# FPGA_Supply.net
KiCad netlist of a schematic drawn in Altium Designer
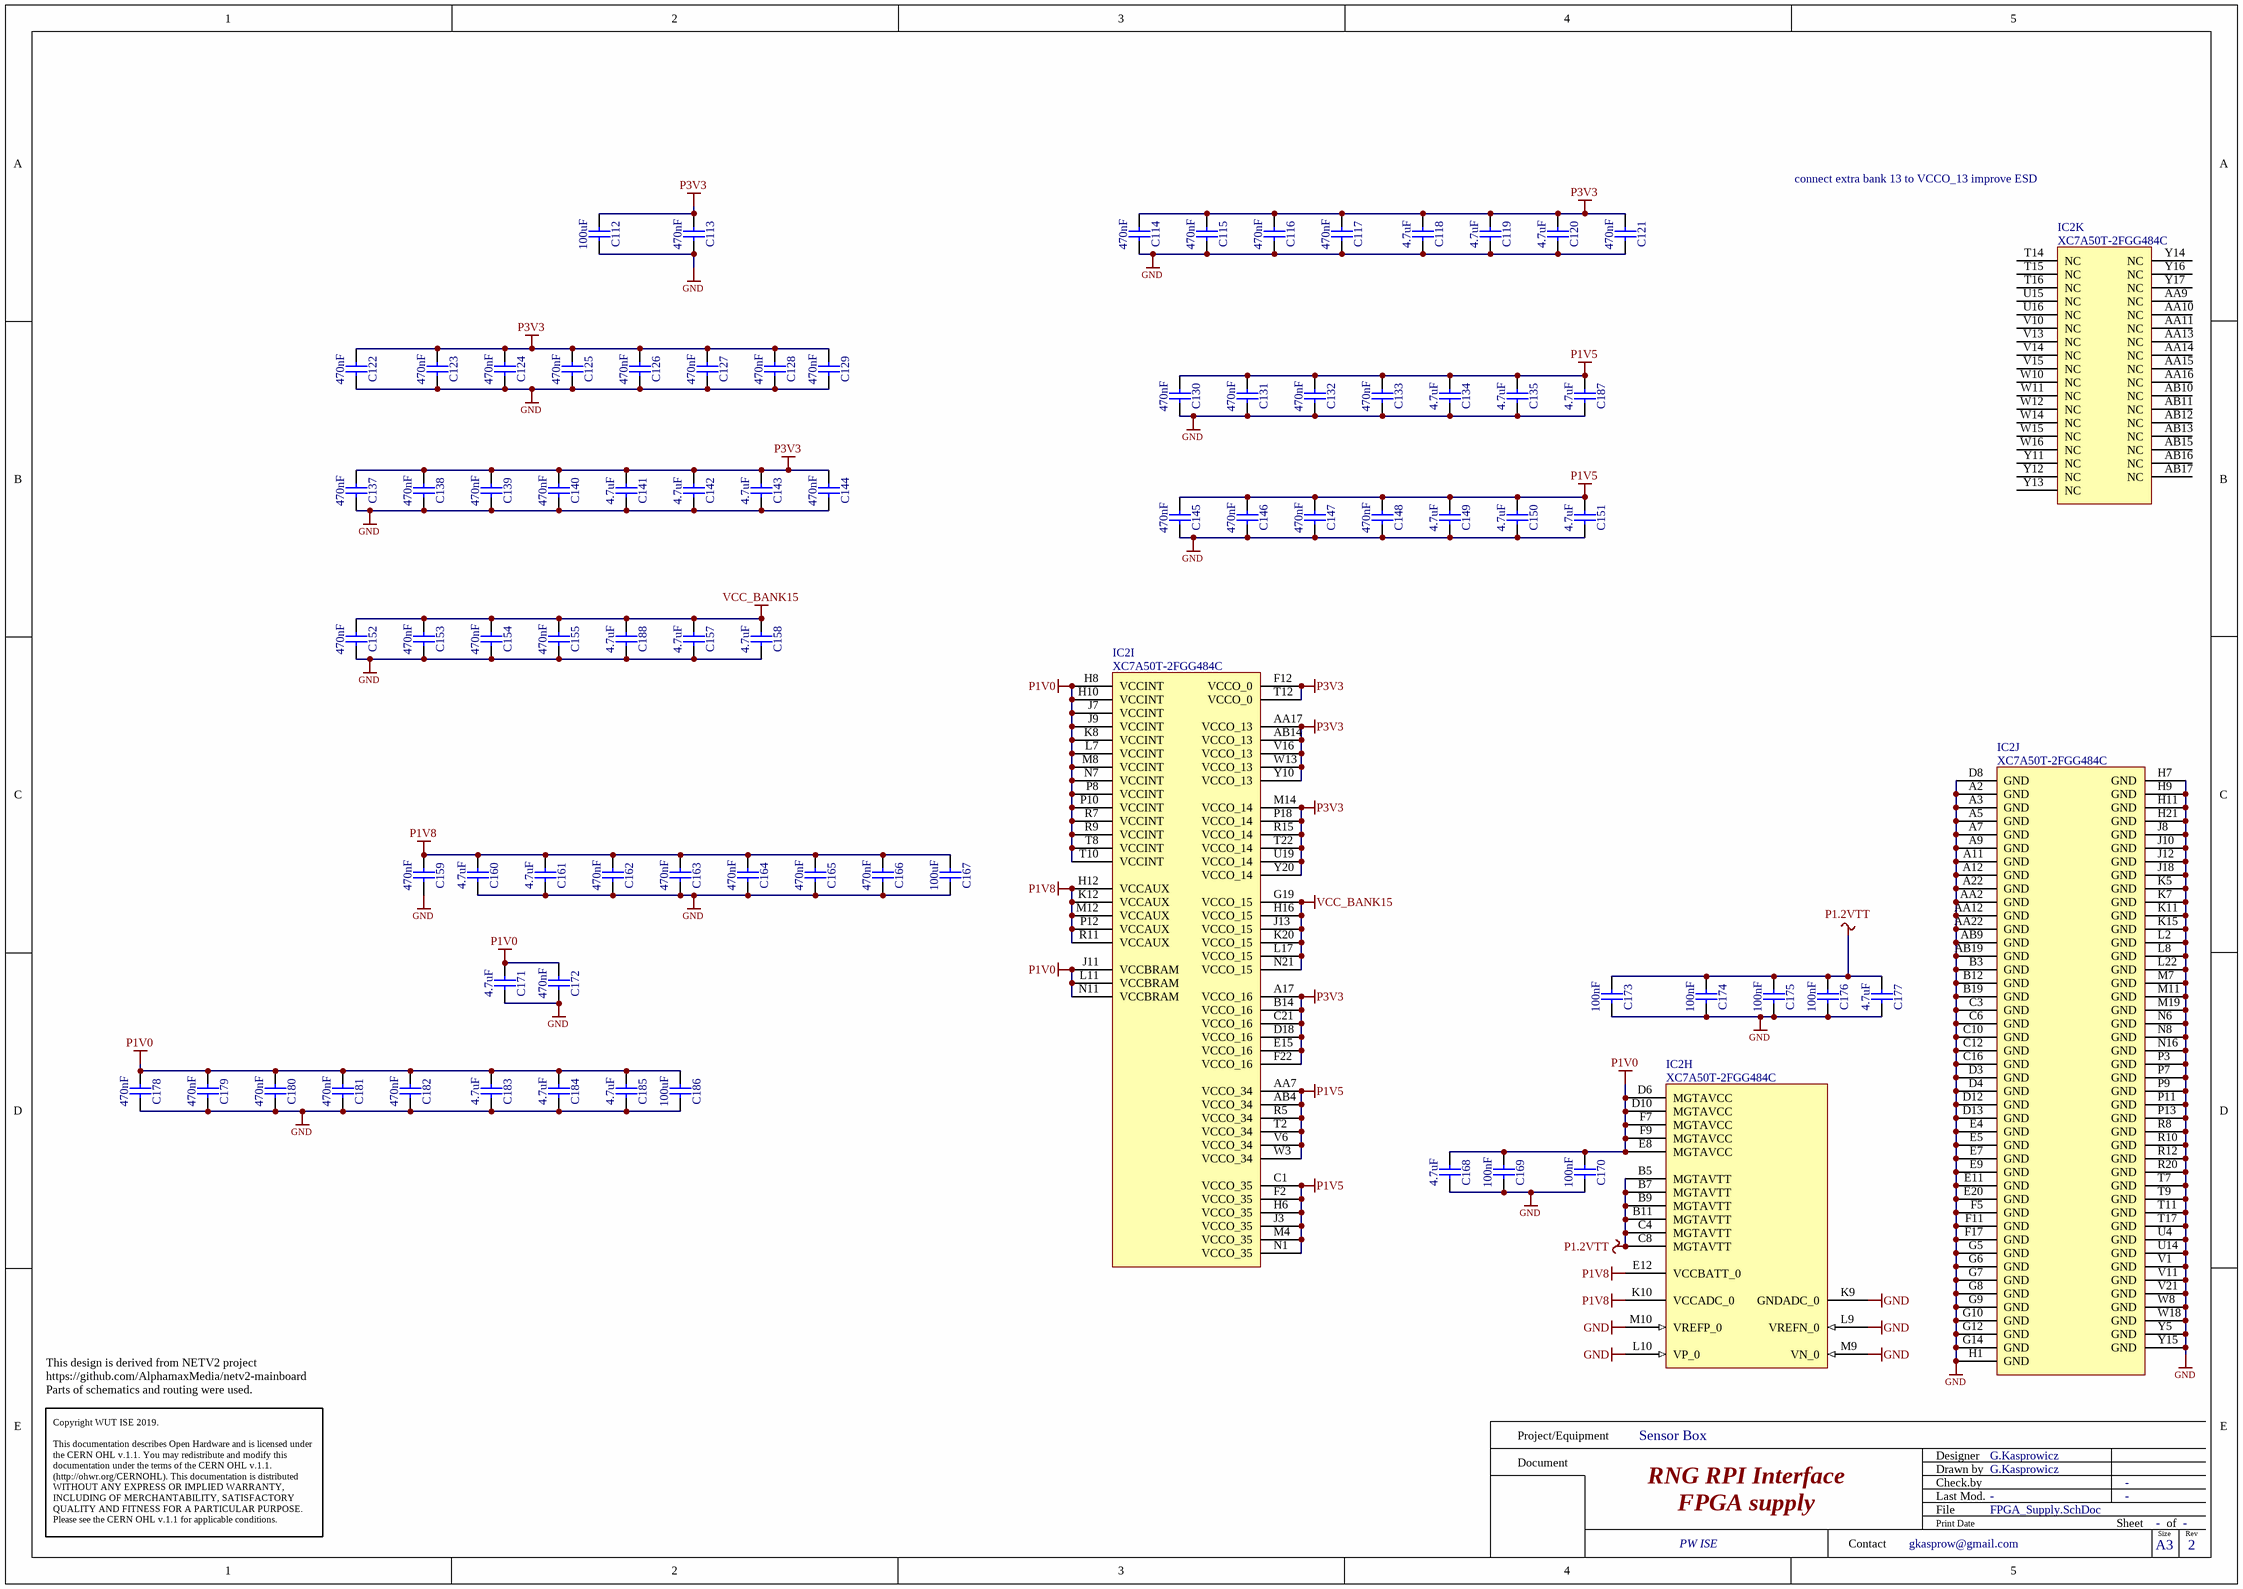
[diagram p0: FPGA_Supply.SchDoc]

(export (version "E")
  (design (tool "Eeschema 10.0.6"))
  (components
    (comp (ref "C112")
      (value "100uF")
      (footprint "CAPC3216X180N")
      (description "Non-polarised capacitor")
      (fields (field (name "PART NUMBER") "CC1206_100UF_6.3V_20%_X5R") (field (name "VOLTAGE") "6.3V"))
      (libsource (lib "Capacitors") (part "Capacitor - non polarized"))
    )
    (comp (ref "C113")
      (value "470nF")
      (footprint "CAPC0603X33N")
      (description "Non-polarised capacitor")
      (fields (field (name "PART NUMBER") "CC0201_470NF_4V_20%_X5R") (field (name "VOLTAGE") "4V"))
      (libsource (lib "Capacitors") (part "Capacitor - non polarized"))
    )
    (comp (ref "C114")
      (value "470nF")
      (footprint "CAPC0603X33N")
      (description "Non-polarised capacitor")
      (fields (field (name "PART NUMBER") "CC0201_470NF_4V_20%_X5R") (field (name "VOLTAGE") "4V"))
      (libsource (lib "Capacitors") (part "Capacitor - non polarized"))
    )
    (comp (ref "C115")
      (value "470nF")
      (footprint "CAPC0603X33N")
      (description "Non-polarised capacitor")
      (fields (field (name "PART NUMBER") "CC0201_470NF_4V_20%_X5R") (field (name "VOLTAGE") "4V"))
      (libsource (lib "Capacitors") (part "Capacitor - non polarized"))
    )
    (comp (ref "C116")
      (value "470nF")
      (footprint "CAPC0603X33N")
      (description "Non-polarised capacitor")
      (fields (field (name "PART NUMBER") "CC0201_470NF_4V_20%_X5R") (field (name "VOLTAGE") "4V"))
      (libsource (lib "Capacitors") (part "Capacitor - non polarized"))
    )
    (comp (ref "C117")
      (value "470nF")
      (footprint "CAPC0603X33N")
      (description "Non-polarised capacitor")
      (fields (field (name "PART NUMBER") "CC0201_470NF_4V_20%_X5R") (field (name "VOLTAGE") "4V"))
      (libsource (lib "Capacitors") (part "Capacitor - non polarized"))
    )
    (comp (ref "C118")
      (value "4.7uF")
      (footprint "CAPC1005X55N")
      (description "Non-polarised capacitor")
      (fields (field (name "PART NUMBER") "CC0402_4.7UF_6.3V_20%_X5R") (field (name "VOLTAGE") "6.3V"))
      (libsource (lib "Capacitors") (part "Capacitor - non polarized"))
    )
    (comp (ref "C119")
      (value "4.7uF")
      (footprint "CAPC1005X55N")
      (description "Non-polarised capacitor")
      (fields (field (name "PART NUMBER") "CC0402_4.7UF_6.3V_20%_X5R") (field (name "VOLTAGE") "6.3V"))
      (libsource (lib "Capacitors") (part "Capacitor - non polarized"))
    )
    (comp (ref "C120")
      (value "4.7uF")
      (footprint "CAPC1005X55N")
      (description "Non-polarised capacitor")
      (fields (field (name "PART NUMBER") "CC0402_4.7UF_6.3V_20%_X5R") (field (name "VOLTAGE") "6.3V"))
      (libsource (lib "Capacitors") (part "Capacitor - non polarized"))
    )
    (comp (ref "C121")
      (value "470nF")
      (footprint "CAPC0603X33N")
      (description "Non-polarised capacitor")
      (fields (field (name "PART NUMBER") "CC0201_470NF_4V_20%_X5R") (field (name "VOLTAGE") "4V"))
      (libsource (lib "Capacitors") (part "Capacitor - non polarized"))
    )
    (comp (ref "C122")
      (value "470nF")
      (footprint "CAPC0603X33N")
      (description "Non-polarised capacitor")
      (fields (field (name "PART NUMBER") "CC0201_470NF_4V_20%_X5R") (field (name "VOLTAGE") "4V"))
      (libsource (lib "Capacitors") (part "Capacitor - non polarized"))
    )
    (comp (ref "C123")
      (value "470nF")
      (footprint "CAPC0603X33N")
      (description "Non-polarised capacitor")
      (fields (field (name "PART NUMBER") "CC0201_470NF_4V_20%_X5R") (field (name "VOLTAGE") "4V"))
      (libsource (lib "Capacitors") (part "Capacitor - non polarized"))
    )
    (comp (ref "C124")
      (value "470nF")
      (footprint "CAPC0603X33N")
      (description "Non-polarised capacitor")
      (fields (field (name "PART NUMBER") "CC0201_470NF_4V_20%_X5R") (field (name "VOLTAGE") "4V"))
      (libsource (lib "Capacitors") (part "Capacitor - non polarized"))
    )
    (comp (ref "C125")
      (value "470nF")
      (footprint "CAPC0603X33N")
      (description "Non-polarised capacitor")
      (fields (field (name "PART NUMBER") "CC0201_470NF_4V_20%_X5R") (field (name "VOLTAGE") "4V"))
      (libsource (lib "Capacitors") (part "Capacitor - non polarized"))
    )
    (comp (ref "C126")
      (value "470nF")
      (footprint "CAPC0603X33N")
      (description "Non-polarised capacitor")
      (fields (field (name "PART NUMBER") "CC0201_470NF_4V_20%_X5R") (field (name "VOLTAGE") "4V"))
      (libsource (lib "Capacitors") (part "Capacitor - non polarized"))
    )
    (comp (ref "C127")
      (value "470nF")
      (footprint "CAPC0603X33N")
      (description "Non-polarised capacitor")
      (fields (field (name "PART NUMBER") "CC0201_470NF_4V_20%_X5R") (field (name "VOLTAGE") "4V"))
      (libsource (lib "Capacitors") (part "Capacitor - non polarized"))
    )
    (comp (ref "C128")
      (value "470nF")
      (footprint "CAPC0603X33N")
      (description "Non-polarised capacitor")
      (fields (field (name "PART NUMBER") "CC0201_470NF_4V_20%_X5R") (field (name "VOLTAGE") "4V"))
      (libsource (lib "Capacitors") (part "Capacitor - non polarized"))
    )
    (comp (ref "C129")
      (value "470nF")
      (footprint "CAPC0603X33N")
      (description "Non-polarised capacitor")
      (fields (field (name "PART NUMBER") "CC0201_470NF_4V_20%_X5R") (field (name "VOLTAGE") "4V"))
      (libsource (lib "Capacitors") (part "Capacitor - non polarized"))
    )
    (comp (ref "C130")
      (value "470nF")
      (footprint "CAPC0603X33N")
      (description "Non-polarised capacitor")
      (fields (field (name "PART NUMBER") "CC0201_470NF_4V_20%_X5R") (field (name "VOLTAGE") "4V"))
      (libsource (lib "Capacitors") (part "Capacitor - non polarized"))
    )
    (comp (ref "C131")
      (value "470nF")
      (footprint "CAPC0603X33N")
      (description "Non-polarised capacitor")
      (fields (field (name "PART NUMBER") "CC0201_470NF_4V_20%_X5R") (field (name "VOLTAGE") "4V"))
      (libsource (lib "Capacitors") (part "Capacitor - non polarized"))
    )
    (comp (ref "C132")
      (value "470nF")
      (footprint "CAPC0603X33N")
      (description "Non-polarised capacitor")
      (fields (field (name "PART NUMBER") "CC0201_470NF_4V_20%_X5R") (field (name "VOLTAGE") "4V"))
      (libsource (lib "Capacitors") (part "Capacitor - non polarized"))
    )
    (comp (ref "C133")
      (value "470nF")
      (footprint "CAPC0603X33N")
      (description "Non-polarised capacitor")
      (fields (field (name "PART NUMBER") "CC0201_470NF_4V_20%_X5R") (field (name "VOLTAGE") "4V"))
      (libsource (lib "Capacitors") (part "Capacitor - non polarized"))
    )
    (comp (ref "C134")
      (value "4.7uF")
      (footprint "CAPC1005X55N")
      (description "Non-polarised capacitor")
      (fields (field (name "PART NUMBER") "CC0402_4.7UF_6.3V_20%_X5R") (field (name "VOLTAGE") "6.3V"))
      (libsource (lib "Capacitors") (part "Capacitor - non polarized"))
    )
    (comp (ref "C135")
      (value "4.7uF")
      (footprint "CAPC1005X55N")
      (description "Non-polarised capacitor")
      (fields (field (name "PART NUMBER") "CC0402_4.7UF_6.3V_20%_X5R") (field (name "VOLTAGE") "6.3V"))
      (libsource (lib "Capacitors") (part "Capacitor - non polarized"))
    )
    (comp (ref "C137")
      (value "470nF")
      (footprint "CAPC0603X33N")
      (description "Non-polarised capacitor")
      (fields (field (name "PART NUMBER") "CC0201_470NF_4V_20%_X5R") (field (name "VOLTAGE") "4V"))
      (libsource (lib "Capacitors") (part "Capacitor - non polarized"))
    )
    (comp (ref "C138")
      (value "470nF")
      (footprint "CAPC0603X33N")
      (description "Non-polarised capacitor")
      (fields (field (name "PART NUMBER") "CC0201_470NF_4V_20%_X5R") (field (name "VOLTAGE") "4V"))
      (libsource (lib "Capacitors") (part "Capacitor - non polarized"))
    )
    (comp (ref "C139")
      (value "470nF")
      (footprint "CAPC0603X33N")
      (description "Non-polarised capacitor")
      (fields (field (name "PART NUMBER") "CC0201_470NF_4V_20%_X5R") (field (name "VOLTAGE") "4V"))
      (libsource (lib "Capacitors") (part "Capacitor - non polarized"))
    )
    (comp (ref "C140")
      (value "470nF")
      (footprint "CAPC0603X33N")
      (description "Non-polarised capacitor")
      (fields (field (name "PART NUMBER") "CC0201_470NF_4V_20%_X5R") (field (name "VOLTAGE") "4V"))
      (libsource (lib "Capacitors") (part "Capacitor - non polarized"))
    )
    (comp (ref "C141")
      (value "4.7uF")
      (footprint "CAPC1005X55N")
      (description "Non-polarised capacitor")
      (fields (field (name "PART NUMBER") "CC0402_4.7UF_6.3V_20%_X5R") (field (name "VOLTAGE") "6.3V"))
      (libsource (lib "Capacitors") (part "Capacitor - non polarized"))
    )
    (comp (ref "C142")
      (value "4.7uF")
      (footprint "CAPC1005X55N")
      (description "Non-polarised capacitor")
      (fields (field (name "PART NUMBER") "CC0402_4.7UF_6.3V_20%_X5R") (field (name "VOLTAGE") "6.3V"))
      (libsource (lib "Capacitors") (part "Capacitor - non polarized"))
    )
    (comp (ref "C143")
      (value "4.7uF")
      (footprint "CAPC1005X55N")
      (description "Non-polarised capacitor")
      (fields (field (name "PART NUMBER") "CC0402_4.7UF_6.3V_20%_X5R") (field (name "VOLTAGE") "6.3V"))
      (libsource (lib "Capacitors") (part "Capacitor - non polarized"))
    )
    (comp (ref "C144")
      (value "470nF")
      (footprint "CAPC0603X33N")
      (description "Non-polarised capacitor")
      (fields (field (name "PART NUMBER") "CC0201_470NF_4V_20%_X5R") (field (name "VOLTAGE") "4V"))
      (libsource (lib "Capacitors") (part "Capacitor - non polarized"))
    )
    (comp (ref "C145")
      (value "470nF")
      (footprint "CAPC0603X33N")
      (description "Non-polarised capacitor")
      (fields (field (name "PART NUMBER") "CC0201_470NF_4V_20%_X5R") (field (name "VOLTAGE") "4V"))
      (libsource (lib "Capacitors") (part "Capacitor - non polarized"))
    )
    (comp (ref "C146")
      (value "470nF")
      (footprint "CAPC0603X33N")
      (description "Non-polarised capacitor")
      (fields (field (name "PART NUMBER") "CC0201_470NF_4V_20%_X5R") (field (name "VOLTAGE") "4V"))
      (libsource (lib "Capacitors") (part "Capacitor - non polarized"))
    )
    (comp (ref "C147")
      (value "470nF")
      (footprint "CAPC0603X33N")
      (description "Non-polarised capacitor")
      (fields (field (name "PART NUMBER") "CC0201_470NF_4V_20%_X5R") (field (name "VOLTAGE") "4V"))
      (libsource (lib "Capacitors") (part "Capacitor - non polarized"))
    )
    (comp (ref "C148")
      (value "470nF")
      (footprint "CAPC0603X33N")
      (description "Non-polarised capacitor")
      (fields (field (name "PART NUMBER") "CC0201_470NF_4V_20%_X5R") (field (name "VOLTAGE") "4V"))
      (libsource (lib "Capacitors") (part "Capacitor - non polarized"))
    )
    (comp (ref "C149")
      (value "4.7uF")
      (footprint "CAPC1005X55N")
      (description "Non-polarised capacitor")
      (fields (field (name "PART NUMBER") "CC0402_4.7UF_6.3V_20%_X5R") (field (name "VOLTAGE") "6.3V"))
      (libsource (lib "Capacitors") (part "Capacitor - non polarized"))
    )
    (comp (ref "C150")
      (value "4.7uF")
      (footprint "CAPC1005X55N")
      (description "Non-polarised capacitor")
      (fields (field (name "PART NUMBER") "CC0402_4.7UF_6.3V_20%_X5R") (field (name "VOLTAGE") "6.3V"))
      (libsource (lib "Capacitors") (part "Capacitor - non polarized"))
    )
    (comp (ref "C151")
      (value "4.7uF")
      (footprint "CAPC1005X55N")
      (description "Non-polarised capacitor")
      (fields (field (name "PART NUMBER") "CC0402_4.7UF_6.3V_20%_X5R") (field (name "VOLTAGE") "6.3V"))
      (libsource (lib "Capacitors") (part "Capacitor - non polarized"))
    )
    (comp (ref "C152")
      (value "470nF")
      (footprint "CAPC0603X33N")
      (description "Non-polarised capacitor")
      (fields (field (name "PART NUMBER") "CC0201_470NF_4V_20%_X5R") (field (name "VOLTAGE") "4V"))
      (libsource (lib "Capacitors") (part "Capacitor - non polarized"))
    )
    (comp (ref "C153")
      (value "470nF")
      (footprint "CAPC0603X33N")
      (description "Non-polarised capacitor")
      (fields (field (name "PART NUMBER") "CC0201_470NF_4V_20%_X5R") (field (name "VOLTAGE") "4V"))
      (libsource (lib "Capacitors") (part "Capacitor - non polarized"))
    )
    (comp (ref "C154")
      (value "470nF")
      (footprint "CAPC0603X33N")
      (description "Non-polarised capacitor")
      (fields (field (name "PART NUMBER") "CC0201_470NF_4V_20%_X5R") (field (name "VOLTAGE") "4V"))
      (libsource (lib "Capacitors") (part "Capacitor - non polarized"))
    )
    (comp (ref "C155")
      (value "470nF")
      (footprint "CAPC0603X33N")
      (description "Non-polarised capacitor")
      (fields (field (name "PART NUMBER") "CC0201_470NF_4V_20%_X5R") (field (name "VOLTAGE") "4V"))
      (libsource (lib "Capacitors") (part "Capacitor - non polarized"))
    )
    (comp (ref "C157")
      (value "4.7uF")
      (footprint "CAPC1005X55N")
      (description "Non-polarised capacitor")
      (fields (field (name "PART NUMBER") "CC0402_4.7UF_6.3V_20%_X5R") (field (name "VOLTAGE") "6.3V"))
      (libsource (lib "Capacitors") (part "Capacitor - non polarized"))
    )
    (comp (ref "C158")
      (value "4.7uF")
      (footprint "CAPC1005X55N")
      (description "Non-polarised capacitor")
      (fields (field (name "PART NUMBER") "CC0402_4.7UF_6.3V_20%_X5R") (field (name "VOLTAGE") "6.3V"))
      (libsource (lib "Capacitors") (part "Capacitor - non polarized"))
    )
    (comp (ref "C159")
      (value "470nF")
      (footprint "CAPC0603X33N")
      (description "Non-polarised capacitor")
      (fields (field (name "PART NUMBER") "CC0201_470NF_4V_20%_X5R") (field (name "VOLTAGE") "4V"))
      (libsource (lib "Capacitors") (part "Capacitor - non polarized"))
    )
    (comp (ref "C160")
      (value "4.7uF")
      (footprint "CAPC1005X55N")
      (description "Non-polarised capacitor")
      (fields (field (name "PART NUMBER") "CC0402_4.7UF_6.3V_20%_X5R") (field (name "VOLTAGE") "6.3V"))
      (libsource (lib "Capacitors") (part "Capacitor - non polarized"))
    )
    (comp (ref "C161")
      (value "4.7uF")
      (footprint "CAPC1005X55N")
      (description "Non-polarised capacitor")
      (fields (field (name "PART NUMBER") "CC0402_4.7UF_6.3V_20%_X5R") (field (name "VOLTAGE") "6.3V"))
      (libsource (lib "Capacitors") (part "Capacitor - non polarized"))
    )
    (comp (ref "C162")
      (value "470nF")
      (footprint "CAPC0603X33N")
      (description "Non-polarised capacitor")
      (fields (field (name "PART NUMBER") "CC0201_470NF_4V_20%_X5R") (field (name "VOLTAGE") "4V"))
      (libsource (lib "Capacitors") (part "Capacitor - non polarized"))
    )
    (comp (ref "C163")
      (value "470nF")
      (footprint "CAPC0603X33N")
      (description "Non-polarised capacitor")
      (fields (field (name "PART NUMBER") "CC0201_470NF_4V_20%_X5R") (field (name "VOLTAGE") "4V"))
      (libsource (lib "Capacitors") (part "Capacitor - non polarized"))
    )
    (comp (ref "C164")
      (value "470nF")
      (footprint "CAPC0603X33N")
      (description "Non-polarised capacitor")
      (fields (field (name "PART NUMBER") "CC0201_470NF_4V_20%_X5R") (field (name "VOLTAGE") "4V"))
      (libsource (lib "Capacitors") (part "Capacitor - non polarized"))
    )
    (comp (ref "C165")
      (value "470nF")
      (footprint "CAPC0603X33N")
      (description "Non-polarised capacitor")
      (fields (field (name "PART NUMBER") "CC0201_470NF_4V_20%_X5R") (field (name "VOLTAGE") "4V"))
      (libsource (lib "Capacitors") (part "Capacitor - non polarized"))
    )
    (comp (ref "C166")
      (value "470nF")
      (footprint "CAPC0603X33N")
      (description "Non-polarised capacitor")
      (fields (field (name "PART NUMBER") "CC0201_470NF_4V_20%_X5R") (field (name "VOLTAGE") "4V"))
      (libsource (lib "Capacitors") (part "Capacitor - non polarized"))
    )
    (comp (ref "C167")
      (value "100uF")
      (footprint "CAPC3216X180N")
      (description "Non-polarised capacitor")
      (fields (field (name "PART NUMBER") "CC1206_100UF_6.3V_20%_X5R") (field (name "VOLTAGE") "6.3V"))
      (libsource (lib "Capacitors") (part "Capacitor - non polarized"))
    )
    (comp (ref "C168")
      (value "4.7uF")
      (footprint "CAPC1005X55N")
      (description "Non-polarised capacitor")
      (fields (field (name "PART NUMBER") "CC0402_4.7UF_6.3V_20%_X5R") (field (name "VOLTAGE") "6.3V"))
      (libsource (lib "Capacitors") (part "Capacitor - non polarized"))
    )
    (comp (ref "C169")
      (value "100nF")
      (footprint "CAPC0603X33N")
      (description "Non-polarised capacitor")
      (fields (field (name "PART NUMBER") "CC0201_100NF_6.3V_10%_X5R") (field (name "VOLTAGE") "6.3V"))
      (libsource (lib "Capacitors") (part "Capacitor - non polarized"))
    )
    (comp (ref "C170")
      (value "100nF")
      (footprint "CAPC0603X33N")
      (description "Non-polarised capacitor")
      (fields (field (name "PART NUMBER") "CC0201_100NF_6.3V_10%_X5R") (field (name "VOLTAGE") "6.3V"))
      (libsource (lib "Capacitors") (part "Capacitor - non polarized"))
    )
    (comp (ref "C171")
      (value "4.7uF")
      (footprint "CAPC1005X55N")
      (description "Non-polarised capacitor")
      (fields (field (name "PART NUMBER") "CC0402_4.7UF_6.3V_20%_X5R") (field (name "VOLTAGE") "6.3V"))
      (libsource (lib "Capacitors") (part "Capacitor - non polarized"))
    )
    (comp (ref "C172")
      (value "470nF")
      (footprint "CAPC0603X33N")
      (description "Non-polarised capacitor")
      (fields (field (name "PART NUMBER") "CC0201_470NF_4V_20%_X5R") (field (name "VOLTAGE") "4V"))
      (libsource (lib "Capacitors") (part "Capacitor - non polarized"))
    )
    (comp (ref "C173")
      (value "100nF")
      (footprint "CAPC0603X33N")
      (description "Non-polarised capacitor")
      (fields (field (name "PART NUMBER") "CC0201_100NF_6.3V_10%_X5R") (field (name "VOLTAGE") "6.3V"))
      (libsource (lib "Capacitors") (part "Capacitor - non polarized"))
    )
    (comp (ref "C174")
      (value "100nF")
      (footprint "CAPC0603X33N")
      (description "Non-polarised capacitor")
      (fields (field (name "PART NUMBER") "CC0201_100NF_6.3V_10%_X5R") (field (name "VOLTAGE") "6.3V"))
      (libsource (lib "Capacitors") (part "Capacitor - non polarized"))
    )
    (comp (ref "C175")
      (value "100nF")
      (footprint "CAPC0603X33N")
      (description "Non-polarised capacitor")
      (fields (field (name "PART NUMBER") "CC0201_100NF_6.3V_10%_X5R") (field (name "VOLTAGE") "6.3V"))
      (libsource (lib "Capacitors") (part "Capacitor - non polarized"))
    )
    (comp (ref "C176")
      (value "100nF")
      (footprint "CAPC0603X33N")
      (description "Non-polarised capacitor")
      (fields (field (name "PART NUMBER") "CC0201_100NF_6.3V_10%_X5R") (field (name "VOLTAGE") "6.3V"))
      (libsource (lib "Capacitors") (part "Capacitor - non polarized"))
    )
    (comp (ref "C177")
      (value "4.7uF")
      (footprint "CAPC1005X55N")
      (description "Non-polarised capacitor")
      (fields (field (name "PART NUMBER") "CC0402_4.7UF_6.3V_20%_X5R") (field (name "VOLTAGE") "6.3V"))
      (libsource (lib "Capacitors") (part "Capacitor - non polarized"))
    )
    (comp (ref "C178")
      (value "470nF")
      (footprint "CAPC0603X33N")
      (description "Non-polarised capacitor")
      (fields (field (name "PART NUMBER") "CC0201_470NF_4V_20%_X5R") (field (name "VOLTAGE") "4V"))
      (libsource (lib "Capacitors") (part "Capacitor - non polarized"))
    )
    (comp (ref "C179")
      (value "470nF")
      (footprint "CAPC0603X33N")
      (description "Non-polarised capacitor")
      (fields (field (name "PART NUMBER") "CC0201_470NF_4V_20%_X5R") (field (name "VOLTAGE") "4V"))
      (libsource (lib "Capacitors") (part "Capacitor - non polarized"))
    )
    (comp (ref "C180")
      (value "470nF")
      (footprint "CAPC0603X33N")
      (description "Non-polarised capacitor")
      (fields (field (name "PART NUMBER") "CC0201_470NF_4V_20%_X5R") (field (name "VOLTAGE") "4V"))
      (libsource (lib "Capacitors") (part "Capacitor - non polarized"))
    )
    (comp (ref "C181")
      (value "470nF")
      (footprint "CAPC0603X33N")
      (description "Non-polarised capacitor")
      (fields (field (name "PART NUMBER") "CC0201_470NF_4V_20%_X5R") (field (name "VOLTAGE") "4V"))
      (libsource (lib "Capacitors") (part "Capacitor - non polarized"))
    )
    (comp (ref "C182")
      (value "470nF")
      (footprint "CAPC0603X33N")
      (description "Non-polarised capacitor")
      (fields (field (name "PART NUMBER") "CC0201_470NF_4V_20%_X5R") (field (name "VOLTAGE") "4V"))
      (libsource (lib "Capacitors") (part "Capacitor - non polarized"))
    )
    (comp (ref "C183")
      (value "4.7uF")
      (footprint "CAPC1005X55N")
      (description "Non-polarised capacitor")
      (fields (field (name "PART NUMBER") "CC0402_4.7UF_6.3V_20%_X5R") (field (name "VOLTAGE") "6.3V"))
      (libsource (lib "Capacitors") (part "Capacitor - non polarized"))
    )
    (comp (ref "C184")
      (value "4.7uF")
      (footprint "CAPC1005X55N")
      (description "Non-polarised capacitor")
      (fields (field (name "PART NUMBER") "CC0402_4.7UF_6.3V_20%_X5R") (field (name "VOLTAGE") "6.3V"))
      (libsource (lib "Capacitors") (part "Capacitor - non polarized"))
    )
    (comp (ref "C185")
      (value "4.7uF")
      (footprint "CAPC1005X55N")
      (description "Non-polarised capacitor")
      (fields (field (name "PART NUMBER") "CC0402_4.7UF_6.3V_20%_X5R") (field (name "VOLTAGE") "6.3V"))
      (libsource (lib "Capacitors") (part "Capacitor - non polarized"))
    )
    (comp (ref "C186")
      (value "100uF")
      (footprint "CAPC3216X180N")
      (description "Non-polarised capacitor")
      (fields (field (name "PART NUMBER") "CC1206_100UF_6.3V_20%_X5R") (field (name "VOLTAGE") "6.3V"))
      (libsource (lib "Capacitors") (part "Capacitor - non polarized"))
    )
    (comp (ref "C187")
      (value "4.7uF")
      (footprint "CAPC1005X55N")
      (description "Non-polarised capacitor")
      (fields (field (name "PART NUMBER") "CC0402_4.7UF_6.3V_20%_X5R") (field (name "VOLTAGE") "6.3V"))
      (libsource (lib "Capacitors") (part "Capacitor - non polarized"))
    )
    (comp (ref "C188")
      (value "4.7uF")
      (footprint "CAPC1005X55N")
      (description "Non-polarised capacitor")
      (fields (field (name "PART NUMBER") "CC0402_4.7UF_6.3V_20%_X5R") (field (name "VOLTAGE") "6.3V"))
      (libsource (lib "Capacitors") (part "Capacitor - non polarized"))
    )
    (comp (ref "IC2")
      (value "XC7A50T-2FGG484C")
      (footprint "BGA484C100P22X22_2300X2300X260")
      (fields (field (name "MANUFACTURER") "XILINX"))
      (libsource (lib "ICs And Semiconductors") (part "XC7A50T-2FGG484C"))
    )
  )
  (nets
    (net (code "1") (name "GND") (class "Default")
      (node (ref "C112") (pin "2") (pinfunction "2_2") (pintype "passive"))
      (node (ref "C113") (pin "2") (pinfunction "2_2") (pintype "passive"))
      (node (ref "C114") (pin "2") (pinfunction "2_2") (pintype "passive"))
      (node (ref "C115") (pin "2") (pinfunction "2_2") (pintype "passive"))
      (node (ref "C116") (pin "2") (pinfunction "2_2") (pintype "passive"))
      (node (ref "C117") (pin "2") (pinfunction "2_2") (pintype "passive"))
      (node (ref "C118") (pin "2") (pinfunction "2_2") (pintype "passive"))
      (node (ref "C119") (pin "2") (pinfunction "2_2") (pintype "passive"))
      (node (ref "C120") (pin "2") (pinfunction "2_2") (pintype "passive"))
      (node (ref "C121") (pin "2") (pinfunction "2_2") (pintype "passive"))
      (node (ref "C122") (pin "2") (pinfunction "2_2") (pintype "passive"))
      (node (ref "C123") (pin "2") (pinfunction "2_2") (pintype "passive"))
      (node (ref "C124") (pin "2") (pinfunction "2_2") (pintype "passive"))
      (node (ref "C125") (pin "2") (pinfunction "2_2") (pintype "passive"))
      (node (ref "C126") (pin "2") (pinfunction "2_2") (pintype "passive"))
      (node (ref "C127") (pin "2") (pinfunction "2_2") (pintype "passive"))
      (node (ref "C128") (pin "2") (pinfunction "2_2") (pintype "passive"))
      (node (ref "C129") (pin "2") (pinfunction "2_2") (pintype "passive"))
      (node (ref "C130") (pin "2") (pinfunction "2_2") (pintype "passive"))
      (node (ref "C131") (pin "2") (pinfunction "2_2") (pintype "passive"))
      (node (ref "C132") (pin "2") (pinfunction "2_2") (pintype "passive"))
      (node (ref "C133") (pin "2") (pinfunction "2_2") (pintype "passive"))
      (node (ref "C134") (pin "2") (pinfunction "2_2") (pintype "passive"))
      (node (ref "C135") (pin "2") (pinfunction "2_2") (pintype "passive"))
      (node (ref "C137") (pin "2") (pinfunction "2_2") (pintype "passive"))
      (node (ref "C138") (pin "2") (pinfunction "2_2") (pintype "passive"))
      (node (ref "C139") (pin "2") (pinfunction "2_2") (pintype "passive"))
      (node (ref "C140") (pin "2") (pinfunction "2_2") (pintype "passive"))
      (node (ref "C141") (pin "2") (pinfunction "2_2") (pintype "passive"))
      (node (ref "C142") (pin "2") (pinfunction "2_2") (pintype "passive"))
      (node (ref "C143") (pin "2") (pinfunction "2_2") (pintype "passive"))
      (node (ref "C144") (pin "2") (pinfunction "2_2") (pintype "passive"))
      (node (ref "C145") (pin "2") (pinfunction "2_2") (pintype "passive"))
      (node (ref "C146") (pin "2") (pinfunction "2_2") (pintype "passive"))
      (node (ref "C147") (pin "2") (pinfunction "2_2") (pintype "passive"))
      (node (ref "C148") (pin "2") (pinfunction "2_2") (pintype "passive"))
      (node (ref "C149") (pin "2") (pinfunction "2_2") (pintype "passive"))
      (node (ref "C150") (pin "2") (pinfunction "2_2") (pintype "passive"))
      (node (ref "C151") (pin "2") (pinfunction "2_2") (pintype "passive"))
      (node (ref "C152") (pin "2") (pinfunction "2_2") (pintype "passive"))
      (node (ref "C153") (pin "2") (pinfunction "2_2") (pintype "passive"))
      (node (ref "C154") (pin "2") (pinfunction "2_2") (pintype "passive"))
      (node (ref "C155") (pin "2") (pinfunction "2_2") (pintype "passive"))
      (node (ref "C157") (pin "2") (pinfunction "2_2") (pintype "passive"))
      (node (ref "C158") (pin "2") (pinfunction "2_2") (pintype "passive"))
      (node (ref "C159") (pin "2") (pinfunction "2_2") (pintype "passive"))
      (node (ref "C160") (pin "2") (pinfunction "2_2") (pintype "passive"))
      (node (ref "C161") (pin "2") (pinfunction "2_2") (pintype "passive"))
      (node (ref "C162") (pin "2") (pinfunction "2_2") (pintype "passive"))
      (node (ref "C163") (pin "2") (pinfunction "2_2") (pintype "passive"))
      (node (ref "C164") (pin "2") (pinfunction "2_2") (pintype "passive"))
      (node (ref "C165") (pin "2") (pinfunction "2_2") (pintype "passive"))
      (node (ref "C166") (pin "2") (pinfunction "2_2") (pintype "passive"))
      (node (ref "C167") (pin "2") (pinfunction "2_2") (pintype "passive"))
      (node (ref "C168") (pin "2") (pinfunction "2_2") (pintype "passive"))
      (node (ref "C169") (pin "2") (pinfunction "2_2") (pintype "passive"))
      (node (ref "C170") (pin "2") (pinfunction "2_2") (pintype "passive"))
      (node (ref "C171") (pin "2") (pinfunction "2_2") (pintype "passive"))
      (node (ref "C172") (pin "2") (pinfunction "2_2") (pintype "passive"))
      (node (ref "C173") (pin "2") (pinfunction "2_2") (pintype "passive"))
      (node (ref "C174") (pin "2") (pinfunction "2_2") (pintype "passive"))
      (node (ref "C175") (pin "2") (pinfunction "2_2") (pintype "passive"))
      (node (ref "C176") (pin "2") (pinfunction "2_2") (pintype "passive"))
      (node (ref "C177") (pin "2") (pinfunction "2_2") (pintype "passive"))
      (node (ref "C178") (pin "2") (pinfunction "2_2") (pintype "passive"))
      (node (ref "C179") (pin "2") (pinfunction "2_2") (pintype "passive"))
      (node (ref "C180") (pin "2") (pinfunction "2_2") (pintype "passive"))
      (node (ref "C181") (pin "2") (pinfunction "2_2") (pintype "passive"))
      (node (ref "C182") (pin "2") (pinfunction "2_2") (pintype "passive"))
      (node (ref "C183") (pin "2") (pinfunction "2_2") (pintype "passive"))
      (node (ref "C184") (pin "2") (pinfunction "2_2") (pintype "passive"))
      (node (ref "C185") (pin "2") (pinfunction "2_2") (pintype "passive"))
      (node (ref "C186") (pin "2") (pinfunction "2_2") (pintype "passive"))
      (node (ref "C187") (pin "2") (pinfunction "2_2") (pintype "passive"))
      (node (ref "C188") (pin "2") (pinfunction "2_2") (pintype "passive"))
      (node (ref "IC2") (pin "A11") (pinfunction "GND_A11") (pintype "power_in"))
      (node (ref "IC2") (pin "A12") (pinfunction "GND_A12") (pintype "power_in"))
      (node (ref "IC2") (pin "A2") (pinfunction "GND_A2") (pintype "power_in"))
      (node (ref "IC2") (pin "A22") (pinfunction "GND_A22") (pintype "power_in"))
      (node (ref "IC2") (pin "A3") (pinfunction "GND_A3") (pintype "power_in"))
      (node (ref "IC2") (pin "A5") (pinfunction "GND_A5") (pintype "power_in"))
      (node (ref "IC2") (pin "A7") (pinfunction "GND_A7") (pintype "power_in"))
      (node (ref "IC2") (pin "A9") (pinfunction "GND_A9") (pintype "power_in"))
      (node (ref "IC2") (pin "AA12") (pinfunction "GND_AA12") (pintype "power_in"))
      (node (ref "IC2") (pin "AA2") (pinfunction "GND_AA2") (pintype "power_in"))
      (node (ref "IC2") (pin "AA22") (pinfunction "GND_AA22") (pintype "power_in"))
      (node (ref "IC2") (pin "AB19") (pinfunction "GND_AB19") (pintype "power_in"))
      (node (ref "IC2") (pin "AB9") (pinfunction "GND_AB9") (pintype "power_in"))
      (node (ref "IC2") (pin "B12") (pinfunction "GND_B12") (pintype "power_in"))
      (node (ref "IC2") (pin "B19") (pinfunction "GND_B19") (pintype "power_in"))
      (node (ref "IC2") (pin "B3") (pinfunction "GND_B3") (pintype "power_in"))
      (node (ref "IC2") (pin "C10") (pinfunction "GND_C10") (pintype "power_in"))
      (node (ref "IC2") (pin "C12") (pinfunction "GND_C12") (pintype "power_in"))
      (node (ref "IC2") (pin "C16") (pinfunction "GND_C16") (pintype "power_in"))
      (node (ref "IC2") (pin "C3") (pinfunction "GND_C3") (pintype "power_in"))
      (node (ref "IC2") (pin "C6") (pinfunction "GND_C6") (pintype "power_in"))
      (node (ref "IC2") (pin "D12") (pinfunction "GND_D12") (pintype "power_in"))
      (node (ref "IC2") (pin "D13") (pinfunction "GND_D13") (pintype "power_in"))
      (node (ref "IC2") (pin "D3") (pinfunction "GND_D3") (pintype "power_in"))
      (node (ref "IC2") (pin "D4") (pinfunction "GND_D4") (pintype "power_in"))
      (node (ref "IC2") (pin "D8") (pinfunction "GND_D8") (pintype "power_in"))
      (node (ref "IC2") (pin "E11") (pinfunction "GND_E11") (pintype "power_in"))
      (node (ref "IC2") (pin "E20") (pinfunction "GND_E20") (pintype "power_in"))
      (node (ref "IC2") (pin "E4") (pinfunction "GND_E4") (pintype "power_in"))
      (node (ref "IC2") (pin "E5") (pinfunction "GND_E5") (pintype "power_in"))
      (node (ref "IC2") (pin "E7") (pinfunction "GND_E7") (pintype "power_in"))
      (node (ref "IC2") (pin "E9") (pinfunction "GND_E9") (pintype "power_in"))
      (node (ref "IC2") (pin "F11") (pinfunction "GND_F11") (pintype "power_in"))
      (node (ref "IC2") (pin "F17") (pinfunction "GND_F17") (pintype "power_in"))
      (node (ref "IC2") (pin "F5") (pinfunction "GND_F5") (pintype "power_in"))
      (node (ref "IC2") (pin "G10") (pinfunction "GND_G10") (pintype "power_in"))
      (node (ref "IC2") (pin "G12") (pinfunction "GND_G12") (pintype "power_in"))
      (node (ref "IC2") (pin "G14") (pinfunction "GND_G14") (pintype "power_in"))
      (node (ref "IC2") (pin "G5") (pinfunction "GND_G5") (pintype "power_in"))
      (node (ref "IC2") (pin "G6") (pinfunction "GND_G6") (pintype "power_in"))
      (node (ref "IC2") (pin "G7") (pinfunction "GND_G7") (pintype "power_in"))
      (node (ref "IC2") (pin "G8") (pinfunction "GND_G8") (pintype "power_in"))
      (node (ref "IC2") (pin "G9") (pinfunction "GND_G9") (pintype "power_in"))
      (node (ref "IC2") (pin "H1") (pinfunction "GND_H1") (pintype "power_in"))
      (node (ref "IC2") (pin "H11") (pinfunction "GND_H11") (pintype "power_in"))
      (node (ref "IC2") (pin "H21") (pinfunction "GND_H21") (pintype "power_in"))
      (node (ref "IC2") (pin "H7") (pinfunction "GND_H7") (pintype "power_in"))
      (node (ref "IC2") (pin "H9") (pinfunction "GND_H9") (pintype "power_in"))
      (node (ref "IC2") (pin "J10") (pinfunction "GND_J10") (pintype "power_in"))
      (node (ref "IC2") (pin "J12") (pinfunction "GND_J12") (pintype "power_in"))
      (node (ref "IC2") (pin "J18") (pinfunction "GND_J18") (pintype "power_in"))
      (node (ref "IC2") (pin "J8") (pinfunction "GND_J8") (pintype "power_in"))
      (node (ref "IC2") (pin "K11") (pinfunction "GND_K11") (pintype "power_in"))
      (node (ref "IC2") (pin "K15") (pinfunction "GND_K15") (pintype "power_in"))
      (node (ref "IC2") (pin "K5") (pinfunction "GND_K5") (pintype "power_in"))
      (node (ref "IC2") (pin "K7") (pinfunction "GND_K7") (pintype "power_in"))
      (node (ref "IC2") (pin "K9") (pinfunction "GNDADC_0_K9") (pintype "power_in"))
      (node (ref "IC2") (pin "L10") (pinfunction "VP_0_L10") (pintype "input"))
      (node (ref "IC2") (pin "L2") (pinfunction "GND_L2") (pintype "power_in"))
      (node (ref "IC2") (pin "L22") (pinfunction "GND_L22") (pintype "power_in"))
      (node (ref "IC2") (pin "L8") (pinfunction "GND_L8") (pintype "power_in"))
      (node (ref "IC2") (pin "L9") (pinfunction "VREFN_0_L9") (pintype "input"))
      (node (ref "IC2") (pin "M10") (pinfunction "VREFP_0_M10") (pintype "input"))
      (node (ref "IC2") (pin "M11") (pinfunction "GND_M11") (pintype "power_in"))
      (node (ref "IC2") (pin "M19") (pinfunction "GND_M19") (pintype "power_in"))
      (node (ref "IC2") (pin "M7") (pinfunction "GND_M7") (pintype "power_in"))
      (node (ref "IC2") (pin "M9") (pinfunction "VN_0_M9") (pintype "input"))
      (node (ref "IC2") (pin "N16") (pinfunction "GND_N16") (pintype "power_in"))
      (node (ref "IC2") (pin "N6") (pinfunction "GND_N6") (pintype "power_in"))
      (node (ref "IC2") (pin "N8") (pinfunction "GND_N8") (pintype "power_in"))
      (node (ref "IC2") (pin "P11") (pinfunction "GND_P11") (pintype "power_in"))
      (node (ref "IC2") (pin "P13") (pinfunction "GND_P13") (pintype "power_in"))
      (node (ref "IC2") (pin "P3") (pinfunction "GND_P3") (pintype "power_in"))
      (node (ref "IC2") (pin "P7") (pinfunction "GND_P7") (pintype "power_in"))
      (node (ref "IC2") (pin "P9") (pinfunction "GND_P9") (pintype "power_in"))
      (node (ref "IC2") (pin "R10") (pinfunction "GND_R10") (pintype "power_in"))
      (node (ref "IC2") (pin "R12") (pinfunction "GND_R12") (pintype "power_in"))
      (node (ref "IC2") (pin "R20") (pinfunction "GND_R20") (pintype "power_in"))
      (node (ref "IC2") (pin "R8") (pinfunction "GND_R8") (pintype "power_in"))
      (node (ref "IC2") (pin "T11") (pinfunction "GND_T11") (pintype "power_in"))
      (node (ref "IC2") (pin "T17") (pinfunction "GND_T17") (pintype "power_in"))
      (node (ref "IC2") (pin "T7") (pinfunction "GND_T7") (pintype "power_in"))
      (node (ref "IC2") (pin "T9") (pinfunction "GND_T9") (pintype "power_in"))
      (node (ref "IC2") (pin "U14") (pinfunction "GND_U14") (pintype "power_in"))
      (node (ref "IC2") (pin "U4") (pinfunction "GND_U4") (pintype "power_in"))
      (node (ref "IC2") (pin "V1") (pinfunction "GND_V1") (pintype "power_in"))
      (node (ref "IC2") (pin "V11") (pinfunction "GND_V11") (pintype "power_in"))
      (node (ref "IC2") (pin "V21") (pinfunction "GND_V21") (pintype "power_in"))
      (node (ref "IC2") (pin "W18") (pinfunction "GND_W18") (pintype "power_in"))
      (node (ref "IC2") (pin "W8") (pinfunction "GND_W8") (pintype "power_in"))
      (node (ref "IC2") (pin "Y15") (pinfunction "GND_Y15") (pintype "power_in"))
      (node (ref "IC2") (pin "Y5") (pinfunction "GND_Y5") (pintype "power_in"))
    )
    (net (code "2") (name "P1.2VTT") (class "Default")
      (node (ref "C173") (pin "1") (pinfunction "1_1") (pintype "passive"))
      (node (ref "C174") (pin "1") (pinfunction "1_1") (pintype "passive"))
      (node (ref "C175") (pin "1") (pinfunction "1_1") (pintype "passive"))
      (node (ref "C176") (pin "1") (pinfunction "1_1") (pintype "passive"))
      (node (ref "C177") (pin "1") (pinfunction "1_1") (pintype "passive"))
      (node (ref "IC2") (pin "B11") (pinfunction "MGTAVTT_B11") (pintype "power_in"))
      (node (ref "IC2") (pin "B5") (pinfunction "MGTAVTT_B5") (pintype "power_in"))
      (node (ref "IC2") (pin "B7") (pinfunction "MGTAVTT_B7") (pintype "power_in"))
      (node (ref "IC2") (pin "B9") (pinfunction "MGTAVTT_B9") (pintype "power_in"))
      (node (ref "IC2") (pin "C4") (pinfunction "MGTAVTT_C4") (pintype "power_in"))
      (node (ref "IC2") (pin "C8") (pinfunction "MGTAVTT_C8") (pintype "power_in"))
    )
    (net (code "3") (name "P1V0") (class "Default")
      (node (ref "C168") (pin "1") (pinfunction "1_1") (pintype "passive"))
      (node (ref "C169") (pin "1") (pinfunction "1_1") (pintype "passive"))
      (node (ref "C170") (pin "1") (pinfunction "1_1") (pintype "passive"))
      (node (ref "C171") (pin "1") (pinfunction "1_1") (pintype "passive"))
      (node (ref "C172") (pin "1") (pinfunction "1_1") (pintype "passive"))
      (node (ref "C178") (pin "1") (pinfunction "1_1") (pintype "passive"))
      (node (ref "C179") (pin "1") (pinfunction "1_1") (pintype "passive"))
      (node (ref "C180") (pin "1") (pinfunction "1_1") (pintype "passive"))
      (node (ref "C181") (pin "1") (pinfunction "1_1") (pintype "passive"))
      (node (ref "C182") (pin "1") (pinfunction "1_1") (pintype "passive"))
      (node (ref "C183") (pin "1") (pinfunction "1_1") (pintype "passive"))
      (node (ref "C184") (pin "1") (pinfunction "1_1") (pintype "passive"))
      (node (ref "C185") (pin "1") (pinfunction "1_1") (pintype "passive"))
      (node (ref "C186") (pin "1") (pinfunction "1_1") (pintype "passive"))
      (node (ref "IC2") (pin "D10") (pinfunction "MGTAVCC_D10") (pintype "power_in"))
      (node (ref "IC2") (pin "D6") (pinfunction "MGTAVCC_D6") (pintype "power_in"))
      (node (ref "IC2") (pin "E8") (pinfunction "MGTAVCC_E8") (pintype "power_in"))
      (node (ref "IC2") (pin "F7") (pinfunction "MGTAVCC_F7") (pintype "power_in"))
      (node (ref "IC2") (pin "F9") (pinfunction "MGTAVCC_F9") (pintype "power_in"))
      (node (ref "IC2") (pin "H10") (pinfunction "VCCINT_H10") (pintype "power_in"))
      (node (ref "IC2") (pin "H8") (pinfunction "VCCINT_H8") (pintype "power_in"))
      (node (ref "IC2") (pin "J11") (pinfunction "VCCBRAM_J11") (pintype "power_in"))
      (node (ref "IC2") (pin "J7") (pinfunction "VCCINT_J7") (pintype "power_in"))
      (node (ref "IC2") (pin "J9") (pinfunction "VCCINT_J9") (pintype "power_in"))
      (node (ref "IC2") (pin "K8") (pinfunction "VCCINT_K8") (pintype "power_in"))
      (node (ref "IC2") (pin "L11") (pinfunction "VCCBRAM_L11") (pintype "power_in"))
      (node (ref "IC2") (pin "L7") (pinfunction "VCCINT_L7") (pintype "power_in"))
      (node (ref "IC2") (pin "M8") (pinfunction "VCCINT_M8") (pintype "power_in"))
      (node (ref "IC2") (pin "N11") (pinfunction "VCCBRAM_N11") (pintype "power_in"))
      (node (ref "IC2") (pin "N7") (pinfunction "VCCINT_N7") (pintype "power_in"))
      (node (ref "IC2") (pin "P10") (pinfunction "VCCINT_P10") (pintype "power_in"))
      (node (ref "IC2") (pin "P8") (pinfunction "VCCINT_P8") (pintype "power_in"))
      (node (ref "IC2") (pin "R7") (pinfunction "VCCINT_R7") (pintype "power_in"))
      (node (ref "IC2") (pin "R9") (pinfunction "VCCINT_R9") (pintype "power_in"))
      (node (ref "IC2") (pin "T10") (pinfunction "VCCINT_T10") (pintype "power_in"))
      (node (ref "IC2") (pin "T8") (pinfunction "VCCINT_T8") (pintype "power_in"))
    )
    (net (code "4") (name "P1V5") (class "Default")
      (node (ref "C130") (pin "1") (pinfunction "1_1") (pintype "passive"))
      (node (ref "C131") (pin "1") (pinfunction "1_1") (pintype "passive"))
      (node (ref "C132") (pin "1") (pinfunction "1_1") (pintype "passive"))
      (node (ref "C133") (pin "1") (pinfunction "1_1") (pintype "passive"))
      (node (ref "C134") (pin "1") (pinfunction "1_1") (pintype "passive"))
      (node (ref "C135") (pin "1") (pinfunction "1_1") (pintype "passive"))
      (node (ref "C145") (pin "1") (pinfunction "1_1") (pintype "passive"))
      (node (ref "C146") (pin "1") (pinfunction "1_1") (pintype "passive"))
      (node (ref "C147") (pin "1") (pinfunction "1_1") (pintype "passive"))
      (node (ref "C148") (pin "1") (pinfunction "1_1") (pintype "passive"))
      (node (ref "C149") (pin "1") (pinfunction "1_1") (pintype "passive"))
      (node (ref "C150") (pin "1") (pinfunction "1_1") (pintype "passive"))
      (node (ref "C151") (pin "1") (pinfunction "1_1") (pintype "passive"))
      (node (ref "C187") (pin "1") (pinfunction "1_1") (pintype "passive"))
      (node (ref "IC2") (pin "AA7") (pinfunction "VCCO_34_AA7") (pintype "power_in"))
      (node (ref "IC2") (pin "AB4") (pinfunction "VCCO_34_AB4") (pintype "power_in"))
      (node (ref "IC2") (pin "C1") (pinfunction "VCCO_35_C1") (pintype "power_in"))
      (node (ref "IC2") (pin "F2") (pinfunction "VCCO_35_F2") (pintype "power_in"))
      (node (ref "IC2") (pin "H6") (pinfunction "VCCO_35_H6") (pintype "power_in"))
      (node (ref "IC2") (pin "J3") (pinfunction "VCCO_35_J3") (pintype "power_in"))
      (node (ref "IC2") (pin "M4") (pinfunction "VCCO_35_M4") (pintype "power_in"))
      (node (ref "IC2") (pin "N1") (pinfunction "VCCO_35_N1") (pintype "power_in"))
      (node (ref "IC2") (pin "R5") (pinfunction "VCCO_34_R5") (pintype "power_in"))
      (node (ref "IC2") (pin "T2") (pinfunction "VCCO_34_T2") (pintype "power_in"))
      (node (ref "IC2") (pin "V6") (pinfunction "VCCO_34_V6") (pintype "power_in"))
      (node (ref "IC2") (pin "W3") (pinfunction "VCCO_34_W3") (pintype "power_in"))
    )
    (net (code "5") (name "P1V8") (class "Default")
      (node (ref "C159") (pin "1") (pinfunction "1_1") (pintype "passive"))
      (node (ref "C160") (pin "1") (pinfunction "1_1") (pintype "passive"))
      (node (ref "C161") (pin "1") (pinfunction "1_1") (pintype "passive"))
      (node (ref "C162") (pin "1") (pinfunction "1_1") (pintype "passive"))
      (node (ref "C163") (pin "1") (pinfunction "1_1") (pintype "passive"))
      (node (ref "C164") (pin "1") (pinfunction "1_1") (pintype "passive"))
      (node (ref "C165") (pin "1") (pinfunction "1_1") (pintype "passive"))
      (node (ref "C166") (pin "1") (pinfunction "1_1") (pintype "passive"))
      (node (ref "C167") (pin "1") (pinfunction "1_1") (pintype "passive"))
      (node (ref "IC2") (pin "E12") (pinfunction "VCCBATT_0_E12") (pintype "power_in"))
      (node (ref "IC2") (pin "H12") (pinfunction "VCCAUX_H12") (pintype "power_in"))
      (node (ref "IC2") (pin "K10") (pinfunction "VCCADC_0_K10") (pintype "power_in"))
      (node (ref "IC2") (pin "K12") (pinfunction "VCCAUX_K12") (pintype "power_in"))
      (node (ref "IC2") (pin "M12") (pinfunction "VCCAUX_M12") (pintype "power_in"))
      (node (ref "IC2") (pin "P12") (pinfunction "VCCAUX_P12") (pintype "power_in"))
      (node (ref "IC2") (pin "R11") (pinfunction "VCCAUX_R11") (pintype "power_in"))
    )
    (net (code "6") (name "P3V3") (class "Default")
      (node (ref "C112") (pin "1") (pinfunction "1_1") (pintype "passive"))
      (node (ref "C113") (pin "1") (pinfunction "1_1") (pintype "passive"))
      (node (ref "C114") (pin "1") (pinfunction "1_1") (pintype "passive"))
      (node (ref "C115") (pin "1") (pinfunction "1_1") (pintype "passive"))
      (node (ref "C116") (pin "1") (pinfunction "1_1") (pintype "passive"))
      (node (ref "C117") (pin "1") (pinfunction "1_1") (pintype "passive"))
      (node (ref "C118") (pin "1") (pinfunction "1_1") (pintype "passive"))
      (node (ref "C119") (pin "1") (pinfunction "1_1") (pintype "passive"))
      (node (ref "C120") (pin "1") (pinfunction "1_1") (pintype "passive"))
      (node (ref "C121") (pin "1") (pinfunction "1_1") (pintype "passive"))
      (node (ref "C122") (pin "1") (pinfunction "1_1") (pintype "passive"))
      (node (ref "C123") (pin "1") (pinfunction "1_1") (pintype "passive"))
      (node (ref "C124") (pin "1") (pinfunction "1_1") (pintype "passive"))
      (node (ref "C125") (pin "1") (pinfunction "1_1") (pintype "passive"))
      (node (ref "C126") (pin "1") (pinfunction "1_1") (pintype "passive"))
      (node (ref "C127") (pin "1") (pinfunction "1_1") (pintype "passive"))
      (node (ref "C128") (pin "1") (pinfunction "1_1") (pintype "passive"))
      (node (ref "C129") (pin "1") (pinfunction "1_1") (pintype "passive"))
      (node (ref "C137") (pin "1") (pinfunction "1_1") (pintype "passive"))
      (node (ref "C138") (pin "1") (pinfunction "1_1") (pintype "passive"))
      (node (ref "C139") (pin "1") (pinfunction "1_1") (pintype "passive"))
      (node (ref "C140") (pin "1") (pinfunction "1_1") (pintype "passive"))
      (node (ref "C141") (pin "1") (pinfunction "1_1") (pintype "passive"))
      (node (ref "C142") (pin "1") (pinfunction "1_1") (pintype "passive"))
      (node (ref "C143") (pin "1") (pinfunction "1_1") (pintype "passive"))
      (node (ref "C144") (pin "1") (pinfunction "1_1") (pintype "passive"))
      (node (ref "IC2") (pin "A17") (pinfunction "VCCO_16_A17") (pintype "power_in"))
      (node (ref "IC2") (pin "AA17") (pinfunction "VCCO_13_AA17") (pintype "power_in"))
      (node (ref "IC2") (pin "AB14") (pinfunction "VCCO_13_AB14") (pintype "power_in"))
      (node (ref "IC2") (pin "B14") (pinfunction "VCCO_16_B14") (pintype "power_in"))
      (node (ref "IC2") (pin "C21") (pinfunction "VCCO_16_C21") (pintype "power_in"))
      (node (ref "IC2") (pin "D18") (pinfunction "VCCO_16_D18") (pintype "power_in"))
      (node (ref "IC2") (pin "E15") (pinfunction "VCCO_16_E15") (pintype "power_in"))
      (node (ref "IC2") (pin "F12") (pinfunction "VCCO_0_F12") (pintype "power_in"))
      (node (ref "IC2") (pin "F22") (pinfunction "VCCO_16_F22") (pintype "power_in"))
      (node (ref "IC2") (pin "M14") (pinfunction "VCCO_14_M14") (pintype "power_in"))
      (node (ref "IC2") (pin "P18") (pinfunction "VCCO_14_P18") (pintype "power_in"))
      (node (ref "IC2") (pin "R15") (pinfunction "VCCO_14_R15") (pintype "power_in"))
      (node (ref "IC2") (pin "T12") (pinfunction "VCCO_0_T12") (pintype "power_in"))
      (node (ref "IC2") (pin "T22") (pinfunction "VCCO_14_T22") (pintype "power_in"))
      (node (ref "IC2") (pin "U19") (pinfunction "VCCO_14_U19") (pintype "power_in"))
      (node (ref "IC2") (pin "V16") (pinfunction "VCCO_13_V16") (pintype "power_in"))
      (node (ref "IC2") (pin "W13") (pinfunction "VCCO_13_W13") (pintype "power_in"))
      (node (ref "IC2") (pin "Y10") (pinfunction "VCCO_13_Y10") (pintype "power_in"))
      (node (ref "IC2") (pin "Y20") (pinfunction "VCCO_14_Y20") (pintype "power_in"))
    )
    (net (code "7") (name "VCC_BANK15") (class "Default")
      (node (ref "C152") (pin "1") (pinfunction "1_1") (pintype "passive"))
      (node (ref "C153") (pin "1") (pinfunction "1_1") (pintype "passive"))
      (node (ref "C154") (pin "1") (pinfunction "1_1") (pintype "passive"))
      (node (ref "C155") (pin "1") (pinfunction "1_1") (pintype "passive"))
      (node (ref "C157") (pin "1") (pinfunction "1_1") (pintype "passive"))
      (node (ref "C158") (pin "1") (pinfunction "1_1") (pintype "passive"))
      (node (ref "C188") (pin "1") (pinfunction "1_1") (pintype "passive"))
      (node (ref "IC2") (pin "G19") (pinfunction "VCCO_15_G19") (pintype "power_in"))
      (node (ref "IC2") (pin "H16") (pinfunction "VCCO_15_H16") (pintype "power_in"))
      (node (ref "IC2") (pin "J13") (pinfunction "VCCO_15_J13") (pintype "power_in"))
      (node (ref "IC2") (pin "K20") (pinfunction "VCCO_15_K20") (pintype "power_in"))
      (node (ref "IC2") (pin "L17") (pinfunction "VCCO_15_L17") (pintype "power_in"))
      (node (ref "IC2") (pin "N21") (pinfunction "VCCO_15_N21") (pintype "power_in"))
    )
    (net (code "8") (name "unconnected-(IC2K-NC-PadAA9)") (class "Default")
      (node (ref "IC2") (pin "AA9") (pinfunction "NC_AA9") (pintype "passive"))
    )
    (net (code "9") (name "unconnected-(IC2K-NC-PadAA10)") (class "Default")
      (node (ref "IC2") (pin "AA10") (pinfunction "NC_AA10") (pintype "passive"))
    )
    (net (code "10") (name "unconnected-(IC2K-NC-PadAA11)") (class "Default")
      (node (ref "IC2") (pin "AA11") (pinfunction "NC_AA11") (pintype "passive"))
    )
    (net (code "11") (name "unconnected-(IC2K-NC-PadAA13)") (class "Default")
      (node (ref "IC2") (pin "AA13") (pinfunction "NC_AA13") (pintype "passive"))
    )
    (net (code "12") (name "unconnected-(IC2K-NC-PadAA14)") (class "Default")
      (node (ref "IC2") (pin "AA14") (pinfunction "NC_AA14") (pintype "passive"))
    )
    (net (code "13") (name "unconnected-(IC2K-NC-PadAA15)") (class "Default")
      (node (ref "IC2") (pin "AA15") (pinfunction "NC_AA15") (pintype "passive"))
    )
    (net (code "14") (name "unconnected-(IC2K-NC-PadAA16)") (class "Default")
      (node (ref "IC2") (pin "AA16") (pinfunction "NC_AA16") (pintype "passive"))
    )
    (net (code "15") (name "unconnected-(IC2K-NC-PadAB10)") (class "Default")
      (node (ref "IC2") (pin "AB10") (pinfunction "NC_AB10") (pintype "passive"))
    )
    (net (code "16") (name "unconnected-(IC2K-NC-PadAB11)") (class "Default")
      (node (ref "IC2") (pin "AB11") (pinfunction "NC_AB11") (pintype "passive"))
    )
    (net (code "17") (name "unconnected-(IC2K-NC-PadAB12)") (class "Default")
      (node (ref "IC2") (pin "AB12") (pinfunction "NC_AB12") (pintype "passive"))
    )
    (net (code "18") (name "unconnected-(IC2K-NC-PadAB13)") (class "Default")
      (node (ref "IC2") (pin "AB13") (pinfunction "NC_AB13") (pintype "passive"))
    )
    (net (code "19") (name "unconnected-(IC2K-NC-PadAB15)") (class "Default")
      (node (ref "IC2") (pin "AB15") (pinfunction "NC_AB15") (pintype "passive"))
    )
    (net (code "20") (name "unconnected-(IC2K-NC-PadAB16)") (class "Default")
      (node (ref "IC2") (pin "AB16") (pinfunction "NC_AB16") (pintype "passive"))
    )
    (net (code "21") (name "unconnected-(IC2K-NC-PadAB17)") (class "Default")
      (node (ref "IC2") (pin "AB17") (pinfunction "NC_AB17") (pintype "passive"))
    )
    (net (code "22") (name "unconnected-(IC2K-NC-PadT14)") (class "Default")
      (node (ref "IC2") (pin "T14") (pinfunction "NC_T14") (pintype "passive"))
    )
    (net (code "23") (name "unconnected-(IC2K-NC-PadT15)") (class "Default")
      (node (ref "IC2") (pin "T15") (pinfunction "NC_T15") (pintype "passive"))
    )
    (net (code "24") (name "unconnected-(IC2K-NC-PadT16)") (class "Default")
      (node (ref "IC2") (pin "T16") (pinfunction "NC_T16") (pintype "passive"))
    )
    (net (code "25") (name "unconnected-(IC2K-NC-PadU15)") (class "Default")
      (node (ref "IC2") (pin "U15") (pinfunction "NC_U15") (pintype "passive"))
    )
    (net (code "26") (name "unconnected-(IC2K-NC-PadU16)") (class "Default")
      (node (ref "IC2") (pin "U16") (pinfunction "NC_U16") (pintype "passive"))
    )
    (net (code "27") (name "unconnected-(IC2K-NC-PadV10)") (class "Default")
      (node (ref "IC2") (pin "V10") (pinfunction "NC_V10") (pintype "passive"))
    )
    (net (code "28") (name "unconnected-(IC2K-NC-PadV13)") (class "Default")
      (node (ref "IC2") (pin "V13") (pinfunction "NC_V13") (pintype "passive"))
    )
    (net (code "29") (name "unconnected-(IC2K-NC-PadV14)") (class "Default")
      (node (ref "IC2") (pin "V14") (pinfunction "NC_V14") (pintype "passive"))
    )
    (net (code "30") (name "unconnected-(IC2K-NC-PadV15)") (class "Default")
      (node (ref "IC2") (pin "V15") (pinfunction "NC_V15") (pintype "passive"))
    )
    (net (code "31") (name "unconnected-(IC2K-NC-PadW10)") (class "Default")
      (node (ref "IC2") (pin "W10") (pinfunction "NC_W10") (pintype "passive"))
    )
    (net (code "32") (name "unconnected-(IC2K-NC-PadW11)") (class "Default")
      (node (ref "IC2") (pin "W11") (pinfunction "NC_W11") (pintype "passive"))
    )
    (net (code "33") (name "unconnected-(IC2K-NC-PadW12)") (class "Default")
      (node (ref "IC2") (pin "W12") (pinfunction "NC_W12") (pintype "passive"))
    )
    (net (code "34") (name "unconnected-(IC2K-NC-PadW14)") (class "Default")
      (node (ref "IC2") (pin "W14") (pinfunction "NC_W14") (pintype "passive"))
    )
    (net (code "35") (name "unconnected-(IC2K-NC-PadW15)") (class "Default")
      (node (ref "IC2") (pin "W15") (pinfunction "NC_W15") (pintype "passive"))
    )
    (net (code "36") (name "unconnected-(IC2K-NC-PadW16)") (class "Default")
      (node (ref "IC2") (pin "W16") (pinfunction "NC_W16") (pintype "passive"))
    )
    (net (code "37") (name "unconnected-(IC2K-NC-PadY11)") (class "Default")
      (node (ref "IC2") (pin "Y11") (pinfunction "NC_Y11") (pintype "passive"))
    )
    (net (code "38") (name "unconnected-(IC2K-NC-PadY12)") (class "Default")
      (node (ref "IC2") (pin "Y12") (pinfunction "NC_Y12") (pintype "passive"))
    )
    (net (code "39") (name "unconnected-(IC2K-NC-PadY13)") (class "Default")
      (node (ref "IC2") (pin "Y13") (pinfunction "NC_Y13") (pintype "passive"))
    )
    (net (code "40") (name "unconnected-(IC2K-NC-PadY14)") (class "Default")
      (node (ref "IC2") (pin "Y14") (pinfunction "NC_Y14") (pintype "passive"))
    )
    (net (code "41") (name "unconnected-(IC2K-NC-PadY16)") (class "Default")
      (node (ref "IC2") (pin "Y16") (pinfunction "NC_Y16") (pintype "passive"))
    )
    (net (code "42") (name "unconnected-(IC2K-NC-PadY17)") (class "Default")
      (node (ref "IC2") (pin "Y17") (pinfunction "NC_Y17") (pintype "passive"))
    )
  )
)
